# CLK.net
KiCad netlist of a schematic drawn in Altium Designer
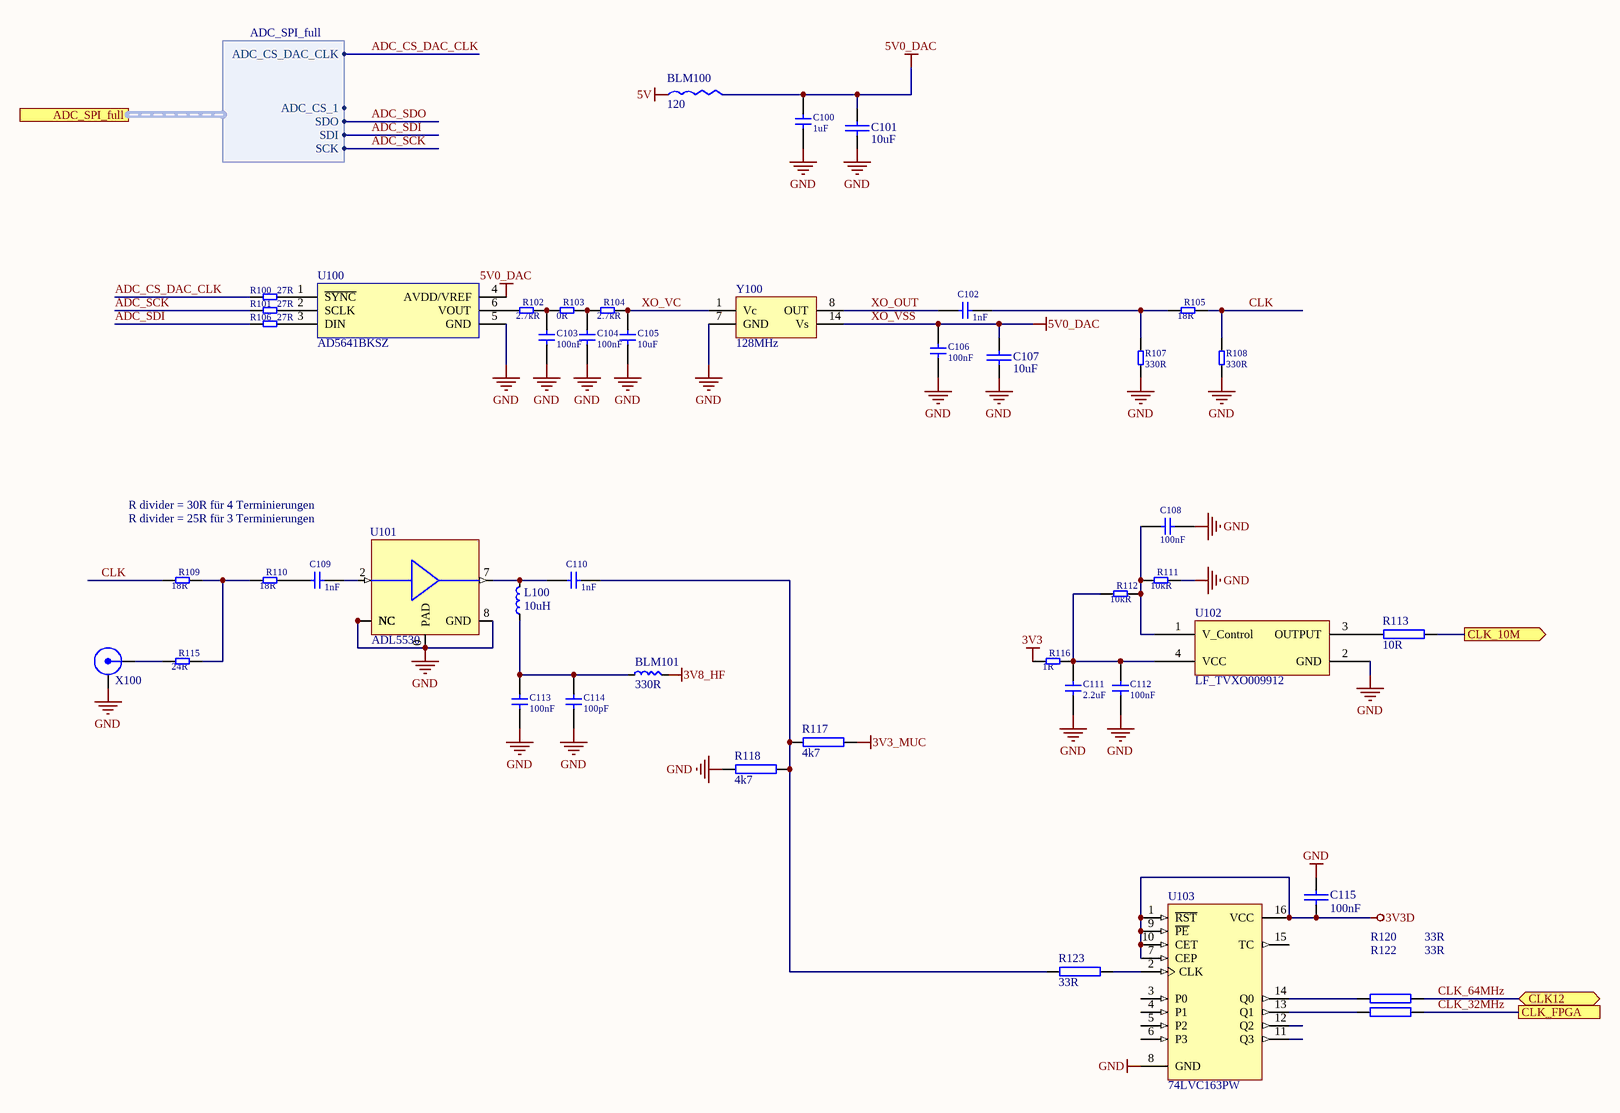
[diagram p0: CLK.SchDoc]

(export (version "E")
  (design (tool "Eeschema 10.0.6"))
  (components
    (comp (ref "BLM100")
      (value "FerriteBeat")
      (footprint "BLM18SG121TN1")
      (description "BLM18SG121TN1")
      (fields (field (name "ALTIUM_UNNAMED_1") "120"))
      (libsource (lib "zynq_board") (part "FerriteBeat"))
    )
    (comp (ref "BLM101")
      (value "330R")
      (footprint "L_0805")
      (description "MPZ2012S331AT000")
      (libsource (lib "zynq_board") (part "MPZ2012S331AT000_BLM_330R"))
    )
    (comp (ref "C100")
      (value "1uF")
      (footprint "C_SMD_0603")
      (description "1uF, 0603, 6.3V, 10%, X5R")
      (fields (field (name "Comment") "SMD capacitor"))
      (libsource (lib "zynq_board") (part "C_SMD"))
    )
    (comp (ref "C101")
      (value "10uF")
      (footprint "0603R")
      (description "MLCC, X5R, 16V, 20%, 0603")
      (fields
        (field (name "PART NUMBER") "10u, 0603, 16V, X5R, 20%")
        (field (name "SOURCE") "SN29500-4, Tabelle 1")
      )
      (libsource (lib "Symeo_libs") (part "_CAP"))
    )
    (comp (ref "C102")
      (value "1nF")
      (footprint "C_SMD_0402")
      (description "1nF, 0402, 6.3V, 10%, X5R")
      (fields (field (name "Comment") "SMD capacitor"))
      (libsource (lib "zynq_board") (part "C_SMD"))
    )
    (comp (ref "C103")
      (value "100nF")
      (footprint "C_SMD_0603")
      (description "100nF, 0603, 50V, 10%, X5R")
      (fields (field (name "Comment") "SMD capacitor"))
      (libsource (lib "zynq_board") (part "C_SMD"))
    )
    (comp (ref "C104")
      (value "100nF")
      (footprint "C_SMD_0603")
      (description "100nF, 0603, 50V, 10%, X5R")
      (fields (field (name "Comment") "SMD capacitor"))
      (libsource (lib "zynq_board") (part "C_SMD"))
    )
    (comp (ref "C105")
      (value "10uF")
      (footprint "C_SMD_1206")
      (description "10uF, 1206, 50V, 20%, X5R")
      (fields (field (name "Comment") "SMD capacitor"))
      (libsource (lib "zynq_board") (part "C_SMD"))
    )
    (comp (ref "C106")
      (value "100nF")
      (footprint "C_SMD_0402")
      (description "100nF, 0402, 6.3V, 10%, X5R")
      (fields (field (name "Comment") "SMD capacitor"))
      (libsource (lib "zynq_board") (part "C_SMD"))
    )
    (comp (ref "C107")
      (value "10uF")
      (footprint "0603R")
      (description "MLCC, X5R, 16V, 20%, 0603")
      (fields
        (field (name "PART NUMBER") "10u, 0603, 16V, X5R, 20%")
        (field (name "SOURCE") "SN29500-4, Tabelle 1")
      )
      (libsource (lib "Symeo_libs") (part "_CAP"))
    )
    (comp (ref "C108")
      (value "100nF")
      (footprint "C_SMD_0603")
      (description "100nF, 0603, 50V, 10%, X5R")
      (fields (field (name "Comment") "SMD capacitor"))
      (libsource (lib "zynq_board") (part "C_SMD"))
    )
    (comp (ref "C109")
      (value "1nF")
      (footprint "C_SMD_0402")
      (description "1nF, 0402, 6.3V, 10%, X5R")
      (fields (field (name "Comment") "SMD capacitor"))
      (libsource (lib "zynq_board") (part "C_SMD"))
    )
    (comp (ref "C110")
      (value "1nF")
      (footprint "C_SMD_0402")
      (description "1nF, 0402, 6.3V, 10%, X5R")
      (fields (field (name "Comment") "SMD capacitor"))
      (libsource (lib "zynq_board") (part "C_SMD"))
    )
    (comp (ref "C111")
      (value "2.2uF")
      (footprint "C_SMD_0603")
      (description "2.2uF, 0603, 6.3V, 10%, X5R")
      (fields (field (name "Comment") "SMD capacitor"))
      (libsource (lib "zynq_board") (part "C_SMD"))
    )
    (comp (ref "C112")
      (value "100nF")
      (footprint "C_SMD_0603")
      (description "100nF, 0603, 50V, 10%, X5R")
      (fields (field (name "Comment") "SMD capacitor"))
      (libsource (lib "zynq_board") (part "C_SMD"))
    )
    (comp (ref "C113")
      (value "100nF")
      (footprint "C_SMD_0402")
      (description "100nF, 0402 50V, 10%, X5R")
      (fields (field (name "Comment") "SMD capacitor"))
      (libsource (lib "zynq_board") (part "C_SMD"))
    )
    (comp (ref "C114")
      (value "100pF")
      (footprint "C_SMD_0402")
      (description "100pF, 0402, 50V, 10%, C0G/NP0")
      (fields (field (name "Comment") "SMD capacitor"))
      (libsource (lib "zynq_board") (part "C_SMD"))
    )
    (comp (ref "C115")
      (value "100nF")
      (footprint "0402RN")
      (description "MLCC, X7R, 50V, 10%, 0402")
      (fields (field (name "PART NUMBER") "100n, 0402, 50V, X7R"))
      (libsource (lib "Symeo_libs") (part "_CAP"))
    )
    (comp (ref "L100")
      (value "10uH")
      (footprint "WE-MI SMD Multilayer Inductor")
      (description "7447908, WE Inductor")
      (libsource (lib "zynq_board") (part "7447908_L_10u"))
    )
    (comp (ref "R100")
      (value "27R")
      (footprint "R_SMD_0402")
      (description "27R, 0402, 1%")
      (fields (field (name "Comment") "SMD Resistor"))
      (libsource (lib "zynq_board") (part "R_SMD"))
    )
    (comp (ref "R101")
      (value "27R")
      (footprint "R_SMD_0402")
      (description "27R, 0402, 1%")
      (fields (field (name "Comment") "SMD Resistor"))
      (libsource (lib "zynq_board") (part "R_SMD"))
    )
    (comp (ref "R102")
      (value "2.7kR")
      (footprint "R_SMD_0402")
      (description "2.7kR, 0402, 1%")
      (fields (field (name "Comment") "SMD Resistor"))
      (libsource (lib "zynq_board") (part "R_SMD"))
    )
    (comp (ref "R103")
      (value "0R")
      (footprint "R_SMD_0402")
      (description "0R, 0402, 1%")
      (fields (field (name "Comment") "SMD Resistor"))
      (libsource (lib "zynq_board") (part "R_SMD"))
    )
    (comp (ref "R104")
      (value "2.7kR")
      (footprint "R_SMD_0402")
      (description "2.7kR, 0402, 1%")
      (fields (field (name "Comment") "SMD Resistor"))
      (libsource (lib "zynq_board") (part "R_SMD"))
    )
    (comp (ref "R105")
      (value "18R")
      (footprint "R_SMD_0402")
      (description "18R, 0402, 1%")
      (fields (field (name "Comment") "SMD Resistor"))
      (libsource (lib "zynq_board") (part "R_SMD"))
    )
    (comp (ref "R106")
      (value "27R")
      (footprint "R_SMD_0402")
      (description "27R, 0402, 1%")
      (fields (field (name "Comment") "SMD Resistor"))
      (libsource (lib "zynq_board") (part "R_SMD"))
    )
    (comp (ref "R107")
      (value "330R")
      (footprint "R_SMD_0402")
      (description "330R, 0402, 1%")
      (fields (field (name "Comment") "SMD Resistor"))
      (libsource (lib "zynq_board") (part "R_SMD"))
    )
    (comp (ref "R108")
      (value "330R")
      (footprint "R_SMD_0402")
      (description "330R, 0402, 1%")
      (fields (field (name "Comment") "SMD Resistor"))
      (libsource (lib "zynq_board") (part "R_SMD"))
    )
    (comp (ref "R109")
      (value "18R")
      (footprint "R_SMD_0402")
      (description "18R, 0402, 1%")
      (fields (field (name "Comment") "SMD Resistor"))
      (libsource (lib "zynq_board") (part "R_SMD"))
    )
    (comp (ref "R110")
      (value "18R")
      (footprint "R_SMD_0402")
      (description "18R, 0402, 1%")
      (fields (field (name "Comment") "SMD Resistor"))
      (libsource (lib "zynq_board") (part "R_SMD"))
    )
    (comp (ref "R111")
      (value "10kR")
      (footprint "R_SMD_0402")
      (description "10kR, 0402, 1%")
      (fields (field (name "Comment") "SMD Resistor"))
      (libsource (lib "zynq_board") (part "R_SMD"))
    )
    (comp (ref "R112")
      (value "10kR")
      (footprint "R_SMD_0402")
      (description "10kR, 0402, 1%")
      (fields (field (name "Comment") "SMD Resistor"))
      (libsource (lib "zynq_board") (part "R_SMD"))
    )
    (comp (ref "R113")
      (value "10R")
      (footprint "0402RN")
      (description "1%, 0.063W, 50V, 0402")
      (fields (field (name "PART NUMBER") "10R, 0402, 1%, 0.063W, 50V"))
      (libsource (lib "Symeo_libs") (part "_RES"))
    )
    (comp (ref "R115")
      (value "24R")
      (footprint "R_SMD_0402")
      (description "24R, 0402, 1%")
      (fields (field (name "Comment") "SMD Resistor"))
      (libsource (lib "zynq_board") (part "R_SMD"))
    )
    (comp (ref "R116")
      (value "1R")
      (footprint "R_SMD_0402")
      (description "1R, 0402, 1%")
      (fields (field (name "Comment") "SMD Resistor"))
      (libsource (lib "zynq_board") (part "R_SMD"))
    )
    (comp (ref "R117")
      (value "4k7")
      (footprint "0402RN")
      (description "1%, 0.063W, 50V, 0402")
      (fields (field (name "PART NUMBER") "4k7, 0402, 1%, 0.063W, 50V"))
      (libsource (lib "Symeo_libs") (part "_RES"))
    )
    (comp (ref "R118")
      (value "4k7")
      (footprint "0402RN")
      (description "1%, 0.063W, 50V, 0402")
      (fields (field (name "PART NUMBER") "4k7, 0402, 1%, 0.063W, 50V"))
      (libsource (lib "Symeo_libs") (part "_RES"))
    )
    (comp (ref "R120")
      (value "33R")
      (footprint "0402RN")
      (description "1%, 0.063W, 50V, 0402")
      (fields (field (name "PART NUMBER") "33R, 0402, 1%, 0.063W, 50V"))
      (libsource (lib "Symeo_libs") (part "_RES"))
    )
    (comp (ref "R122")
      (value "33R")
      (footprint "0402RN")
      (description "1%, 0.063W, 50V, 0402")
      (fields (field (name "PART NUMBER") "33R, 0402, 1%, 0.063W, 50V"))
      (libsource (lib "Symeo_libs") (part "_RES"))
    )
    (comp (ref "R123")
      (value "33R")
      (footprint "0402RN")
      (description "1%, 0.063W, 50V, 0402")
      (fields (field (name "PART NUMBER") "33R, 0402, 1%, 0.063W, 50V"))
      (libsource (lib "Symeo_libs") (part "_RES"))
    )
    (comp (ref "U100")
      (value "AD5641BKSZ")
      (footprint "SC70-LT6_L")
      (description "DAC, 14bit, +-4LSB INL, SPI, SC70")
      (fields (field (name "PART NUMBER") "DAC_AD5641BKSZ") (field (name "SOURCE") "SN29500-2, Tab. 5"))
      (libsource (lib "Symeo_libs") (part "DAC8311"))
    )
    (comp (ref "U101")
      (value "ADL5530")
      (footprint "LFCSP_CP-8-1")
      (description "IF Gain Block; DC-1GHz, 3-5 Volt")
      (libsource (lib "Symeo_libs") (part "ADL5530"))
    )
    (comp (ref "U102")
      (value "LF_TVXO009912")
      (footprint "CFPT-126")
      (libsource (lib "zynq_board") (part "LF_TVXO009912"))
    )
    (comp (ref "U103")
      (value "74LVC163PW")
      (footprint "TSSOP-16")
      (description "Synchronous 4-bit binary conter")
      (fields (field (name "PART NUMBER") "Counter - 74LVC163") (field (name "PUBLISHER") "Altium Limited"))
      (libsource (lib "Symeo_libs") (part "MC74ACT163D"))
    )
    (comp (ref "X100")
      (value "U.FL-R-SMT")
      (footprint "U.FL-R-SMT(01)")
      (description "U.FL Connector U.FL-R-SMT(01), 6GHz, 50R")
      (fields (field (name "PART NUMBER") "Connector - U.FL-R-SMT"))
      (libsource (lib "Symeo_libs") (part "BNC"))
    )
    (comp (ref "Y100")
      (value "128MHz")
      (footprint "VX7-355S-15")
      (description "VX7-355S-15 128MHz")
      (libsource (lib "zynq_board") (part "VX7-355S-15, 128MHz"))
    )
  )
  (nets
    (net (code "2") (name "/ADC_CS_DAC_CLK") (class "Default")
      (node (ref "R100") (pin "2") (pinfunction "2_2") (pintype "passive"))
    )
    (net (code "3") (name "/ADC_SCK") (class "Default")
      (node (ref "R101") (pin "2") (pinfunction "2_2") (pintype "passive"))
    )
    (net (code "4") (name "/ADC_SDI") (class "Default")
      (node (ref "R106") (pin "2") (pinfunction "2_2") (pintype "passive"))
    )
    (net (code "6") (name "/CLK") (class "Default")
      (node (ref "R105") (pin "1") (pinfunction "1_1") (pintype "passive"))
      (node (ref "R108") (pin "1") (pinfunction "1_1") (pintype "passive"))
      (node (ref "R109") (pin "2") (pinfunction "2_2") (pintype "passive"))
    )
    (net (code "7") (name "/CLK_10M") (class "Default") (node (ref "R113") (pin "2") (pintype "passive")))
    (net (code "8") (name "/CLK_32MHz") (class "Default") (node (ref "R122") (pin "2") (pintype "passive")))
    (net (code "9") (name "/CLK_64MHz") (class "Default") (node (ref "R120") (pin "2") (pintype "passive")))
    (net (code "10") (name "/XO_OUT") (class "Default")
      (node (ref "C102") (pin "1") (pinfunction "1_1") (pintype "passive"))
      (node (ref "Y100") (pin "8") (pinfunction "OUT_8") (pintype "passive"))
    )
    (net (code "11") (name "/XO_VC") (class "Default")
      (node (ref "C105") (pin "1") (pinfunction "1_1") (pintype "passive"))
      (node (ref "R104") (pin "1") (pinfunction "1_1") (pintype "passive"))
      (node (ref "Y100") (pin "1") (pinfunction "Vc_1") (pintype "passive"))
    )
    (net (code "13") (name "3V3") (class "Default")
      (node (ref "R116") (pin "2") (pinfunction "2_2") (pintype "passive"))
    )
    (net (code "14") (name "3V3D") (class "Default")
      (node (ref "C115") (pin "2") (pintype "passive"))
      (node (ref "U103") (pin "1") (pinfunction "~{RST}_1") (pintype "input"))
      (node (ref "U103") (pin "10") (pinfunction "CET_10") (pintype "input"))
      (node (ref "U103") (pin "16") (pinfunction "VCC_16") (pintype "power_in"))
      (node (ref "U103") (pin "7") (pinfunction "CEP_7") (pintype "input"))
      (node (ref "U103") (pin "9") (pinfunction "~{PE}_9") (pintype "input"))
    )
    (net (code "15") (name "3V3_MUC") (class "Default") (node (ref "R117") (pin "2") (pintype "passive")))
    (net (code "16") (name "3V8_HF") (class "Default")
      (node (ref "BLM101") (pin "1") (pinfunction "1_1") (pintype "passive"))
    )
    (net (code "17") (name "5V") (class "Default")
      (node (ref "BLM100") (pin "1") (pinfunction "1_1") (pintype "passive"))
    )
    (net (code "18") (name "5V0_DAC") (class "Default")
      (node (ref "BLM100") (pin "2") (pinfunction "2_2") (pintype "passive"))
      (node (ref "C100") (pin "1") (pinfunction "1_1") (pintype "passive"))
      (node (ref "C101") (pin "1") (pintype "passive"))
      (node (ref "C106") (pin "1") (pinfunction "1_1") (pintype "passive"))
      (node (ref "C107") (pin "1") (pintype "passive"))
      (node (ref "U100") (pin "4") (pinfunction "AVDD/VREF_4") (pintype "passive"))
      (node (ref "Y100") (pin "14") (pinfunction "Vs_14") (pintype "passive"))
    )
    (net (code "19") (name "GND") (class "Default")
      (node (ref "C100") (pin "2") (pinfunction "2_2") (pintype "passive"))
      (node (ref "C101") (pin "2") (pintype "passive"))
      (node (ref "C103") (pin "2") (pinfunction "2_2") (pintype "passive"))
      (node (ref "C104") (pin "2") (pinfunction "2_2") (pintype "passive"))
      (node (ref "C105") (pin "2") (pinfunction "2_2") (pintype "passive"))
      (node (ref "C106") (pin "2") (pinfunction "2_2") (pintype "passive"))
      (node (ref "C107") (pin "2") (pintype "passive"))
      (node (ref "C108") (pin "2") (pinfunction "2_2") (pintype "passive"))
      (node (ref "C111") (pin "2") (pinfunction "2_2") (pintype "passive"))
      (node (ref "C112") (pin "2") (pinfunction "2_2") (pintype "passive"))
      (node (ref "C113") (pin "2") (pinfunction "2_2") (pintype "passive"))
      (node (ref "C114") (pin "2") (pinfunction "2_2") (pintype "passive"))
      (node (ref "C115") (pin "1") (pintype "passive"))
      (node (ref "R107") (pin "2") (pinfunction "2_2") (pintype "passive"))
      (node (ref "R108") (pin "2") (pinfunction "2_2") (pintype "passive"))
      (node (ref "R111") (pin "1") (pinfunction "1_1") (pintype "passive"))
      (node (ref "R118") (pin "1") (pintype "passive"))
      (node (ref "U100") (pin "5") (pinfunction "GND_5") (pintype "passive"))
      (node (ref "U101") (pin "0") (pinfunction "PAD_0") (pintype "power_in"))
      (node (ref "U101") (pin "1") (pinfunction "NC_1") (pintype "power_in"))
      (node (ref "U101") (pin "3") (pinfunction "NC_3") (pintype "power_in"))
      (node (ref "U101") (pin "4") (pinfunction "NC_4") (pintype "power_in"))
      (node (ref "U101") (pin "5") (pinfunction "NC_5") (pintype "power_in"))
      (node (ref "U101") (pin "6") (pinfunction "NC_6") (pintype "passive"))
      (node (ref "U101") (pin "8") (pinfunction "GND_8") (pintype "power_in"))
      (node (ref "U102") (pin "2") (pinfunction "GND_2") (pintype "passive"))
      (node (ref "U103") (pin "8") (pinfunction "GND_8") (pintype "power_in"))
      (node (ref "X100") (pin "2") (pintype "passive"))
      (node (ref "Y100") (pin "7") (pinfunction "GND_7") (pintype "passive"))
    )
    (net (code "20") (name "Net-(BLM101-Pad2)") (class "Default")
      (node (ref "BLM101") (pin "2") (pinfunction "2_2") (pintype "passive"))
      (node (ref "C113") (pin "1") (pinfunction "1_1") (pintype "passive"))
      (node (ref "C114") (pin "1") (pinfunction "1_1") (pintype "passive"))
      (node (ref "L100") (pin "2") (pinfunction "2_2") (pintype "passive"))
    )
    (net (code "21") (name "Net-(C102-Pad2)") (class "Default")
      (node (ref "C102") (pin "2") (pinfunction "2_2") (pintype "passive"))
      (node (ref "R105") (pin "2") (pinfunction "2_2") (pintype "passive"))
      (node (ref "R107") (pin "1") (pinfunction "1_1") (pintype "passive"))
    )
    (net (code "22") (name "Net-(C103-Pad1)") (class "Default")
      (node (ref "C103") (pin "1") (pinfunction "1_1") (pintype "passive"))
      (node (ref "R102") (pin "1") (pinfunction "1_1") (pintype "passive"))
      (node (ref "R103") (pin "2") (pinfunction "2_2") (pintype "passive"))
    )
    (net (code "23") (name "Net-(C104-Pad1)") (class "Default")
      (node (ref "C104") (pin "1") (pinfunction "1_1") (pintype "passive"))
      (node (ref "R103") (pin "1") (pinfunction "1_1") (pintype "passive"))
      (node (ref "R104") (pin "2") (pinfunction "2_2") (pintype "passive"))
    )
    (net (code "24") (name "Net-(C109-Pad1)") (class "Default")
      (node (ref "C109") (pin "1") (pinfunction "1_1") (pintype "passive"))
      (node (ref "R110") (pin "1") (pinfunction "1_1") (pintype "passive"))
    )
    (net (code "25") (name "Net-(C110-Pad2)") (class "Default")
      (node (ref "C110") (pin "2") (pinfunction "2_2") (pintype "passive"))
      (node (ref "R117") (pin "1") (pintype "passive"))
      (node (ref "R118") (pin "2") (pintype "passive"))
      (node (ref "R123") (pin "1") (pintype "passive"))
    )
    (net (code "26") (name "Net-(R109-Pad1)") (class "Default")
      (node (ref "R109") (pin "1") (pinfunction "1_1") (pintype "passive"))
      (node (ref "R110") (pin "2") (pinfunction "2_2") (pintype "passive"))
      (node (ref "R115") (pin "1") (pinfunction "1_1") (pintype "passive"))
    )
    (net (code "27") (name "Net-(R115-Pad2)") (class "Default")
      (node (ref "R115") (pin "2") (pinfunction "2_2") (pintype "passive"))
      (node (ref "X100") (pin "1") (pintype "passive"))
    )
    (net (code "28") (name "Net-(U100-DIN)") (class "Default")
      (node (ref "R106") (pin "1") (pinfunction "1_1") (pintype "passive"))
      (node (ref "U100") (pin "3") (pinfunction "DIN_3") (pintype "passive"))
    )
    (net (code "29") (name "Net-(U100-SCLK)") (class "Default")
      (node (ref "R101") (pin "1") (pinfunction "1_1") (pintype "passive"))
      (node (ref "U100") (pin "2") (pinfunction "SCLK_2") (pintype "passive"))
    )
    (net (code "30") (name "Net-(U100-VOUT)") (class "Default")
      (node (ref "R102") (pin "2") (pinfunction "2_2") (pintype "passive"))
      (node (ref "U100") (pin "6") (pinfunction "VOUT_6") (pintype "passive"))
    )
    (net (code "31") (name "Net-(U100-~{SYNC})") (class "Default")
      (node (ref "R100") (pin "1") (pinfunction "1_1") (pintype "passive"))
      (node (ref "U100") (pin "1") (pinfunction "~{SYNC}_1") (pintype "power_in"))
    )
    (net (code "32") (name "Net-(U101-IN)") (class "Default")
      (node (ref "C109") (pin "2") (pinfunction "2_2") (pintype "passive"))
      (node (ref "U101") (pin "2") (pinfunction "IN_2") (pintype "input"))
    )
    (net (code "33") (name "Net-(U101-OUT)") (class "Default")
      (node (ref "C110") (pin "1") (pinfunction "1_1") (pintype "passive"))
      (node (ref "L100") (pin "1") (pinfunction "1_1") (pintype "passive"))
      (node (ref "U101") (pin "7") (pinfunction "OUT_7") (pintype "output"))
    )
    (net (code "34") (name "Net-(U102-OUTPUT)") (class "Default")
      (node (ref "R113") (pin "1") (pintype "passive"))
      (node (ref "U102") (pin "3") (pinfunction "OUTPUT_3") (pintype "passive"))
    )
    (net (code "35") (name "Net-(U102-VCC)") (class "Default")
      (node (ref "C111") (pin "1") (pinfunction "1_1") (pintype "passive"))
      (node (ref "C112") (pin "1") (pinfunction "1_1") (pintype "passive"))
      (node (ref "R112") (pin "2") (pinfunction "2_2") (pintype "passive"))
      (node (ref "R116") (pin "1") (pinfunction "1_1") (pintype "passive"))
      (node (ref "U102") (pin "4") (pinfunction "VCC_4") (pintype "passive"))
    )
    (net (code "36") (name "Net-(U102-V_Control)") (class "Default")
      (node (ref "C108") (pin "1") (pinfunction "1_1") (pintype "passive"))
      (node (ref "R111") (pin "2") (pinfunction "2_2") (pintype "passive"))
      (node (ref "R112") (pin "1") (pinfunction "1_1") (pintype "passive"))
      (node (ref "U102") (pin "1") (pinfunction "V_Control_1") (pintype "passive"))
    )
    (net (code "37") (name "Net-(U103-CLK)") (class "Default")
      (node (ref "R123") (pin "2") (pintype "passive"))
      (node (ref "U103") (pin "2") (pinfunction "CLK_2") (pintype "input"))
    )
    (net (code "38") (name "Net-(U103-Q0)") (class "Default")
      (node (ref "R120") (pin "1") (pintype "passive"))
      (node (ref "U103") (pin "14") (pinfunction "Q0_14") (pintype "output"))
    )
    (net (code "39") (name "Net-(U103-Q1)") (class "Default")
      (node (ref "R122") (pin "1") (pintype "passive"))
      (node (ref "U103") (pin "13") (pinfunction "Q1_13") (pintype "output"))
    )
    (net (code "40") (name "unconnected-(U103-P0-Pad3)") (class "Default")
      (node (ref "U103") (pin "3") (pinfunction "P0_3") (pintype "input"))
    )
    (net (code "41") (name "unconnected-(U103-P1-Pad4)") (class "Default")
      (node (ref "U103") (pin "4") (pinfunction "P1_4") (pintype "input"))
    )
    (net (code "42") (name "unconnected-(U103-P2-Pad5)") (class "Default")
      (node (ref "U103") (pin "5") (pinfunction "P2_5") (pintype "input"))
    )
    (net (code "43") (name "unconnected-(U103-P3-Pad6)") (class "Default")
      (node (ref "U103") (pin "6") (pinfunction "P3_6") (pintype "input"))
    )
    (net (code "44") (name "unconnected-(U103-Q2-Pad12)") (class "Default")
      (node (ref "U103") (pin "12") (pinfunction "Q2_12") (pintype "output"))
    )
    (net (code "45") (name "unconnected-(U103-Q3-Pad11)") (class "Default")
      (node (ref "U103") (pin "11") (pinfunction "Q3_11") (pintype "output"))
    )
    (net (code "46") (name "unconnected-(U103-TC-Pad15)") (class "Default")
      (node (ref "U103") (pin "15") (pinfunction "TC_15") (pintype "output"))
    )
  )
)
